# Memory.net
KiCad netlist of a schematic drawn in Altium Designer
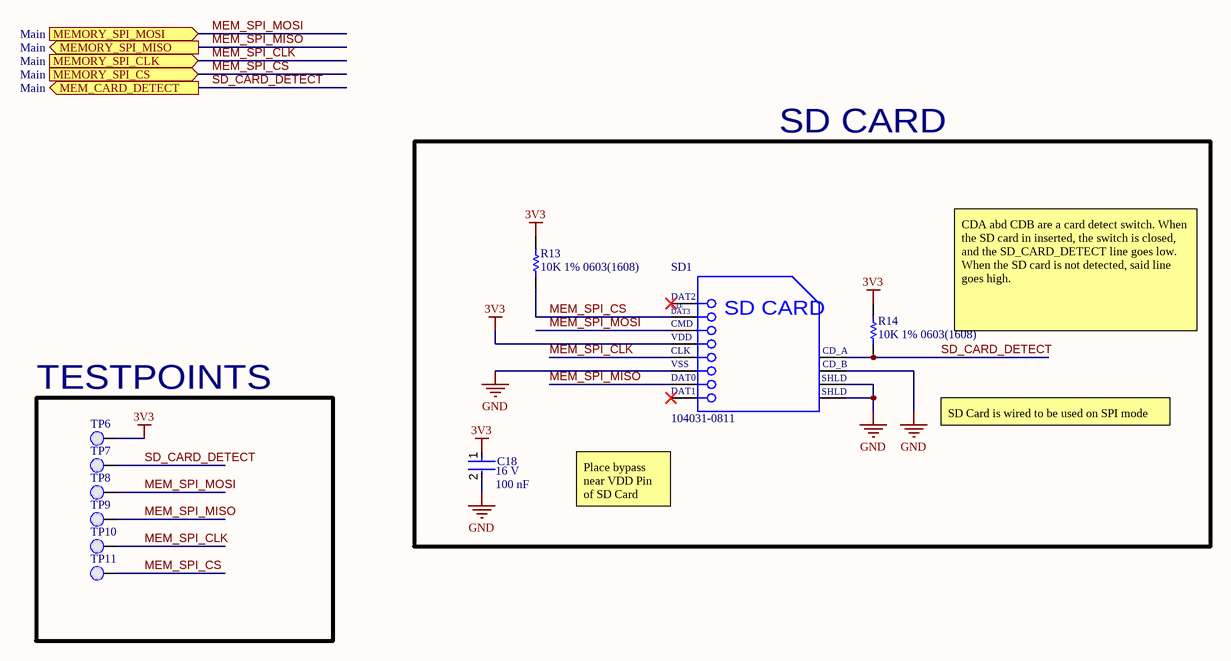
[diagram p0: Memory.SchDoc]

(export (version "E")
  (design (tool "Eeschema 10.0.6"))
  (components
    (comp (ref "C18")
      (value "100 nF")
      (footprint "FP-CC0603-DA-MFG")
      (description "CAP CER 0.1UF 16V X7R 0603")
      (fields
        (field (name "TOLERANCE") "0.1")
        (field (name "VOLTAGE") "16 V")
        (field (name "MANUFACTURER") "YAGEO")
      )
      (libsource (lib "Altium Content Vault") (part "11868f565c42a9108669ba33697ecf6"))
    )
    (comp (ref "R13")
      (value "10K 1% 0603(1608)")
      (footprint "RESC0603(1608)_N")
      (description "10K 0.1W 1% 0603 (1608 Metric)  SMD")
      (fields (field (name "POWER") "0.1 W") (field (name "TOLERANCE") "1 %"))
      (libsource (lib "Altium Content Vault") (part "RES"))
    )
    (comp (ref "R14")
      (value "10K 1% 0603(1608)")
      (footprint "RESC0603(1608)_N")
      (description "10K 0.1W 1% 0603 (1608 Metric)  SMD")
      (fields (field (name "POWER") "0.1 W") (field (name "TOLERANCE") "1 %"))
      (libsource (lib "Altium Content Vault") (part "RES"))
    )
    (comp (ref "SD1")
      (value "104031-0811")
      (footprint "MOLX-104031-0811_V")
      (description "Micro SD Card, RA, -25 to 85 degC, 8-Pin SMD, RoHS, Tape and Reel")
      (fields (field (name "MANUFACTURER") "Molex"))
      (libsource (lib "Altium Content Vault") (part "CN-SD-8-2SW-2S"))
    )
    (comp (ref "TP6")
      (value "0.1\" Pad")
      (footprint "PCBComponent")
      (libsource (lib "Components - 12.02.20 - 18.05") (part "0.1{dblquote} Pad-A.4"))
    )
    (comp (ref "TP7")
      (value "0.1\" Pad")
      (footprint "PCBComponent")
      (libsource (lib "Components - 12.02.20 - 18.05") (part "0.1{dblquote} Pad-A.4"))
    )
    (comp (ref "TP8")
      (value "0.1\" Pad")
      (footprint "PCBComponent")
      (libsource (lib "Components - 12.02.20 - 18.05") (part "0.1{dblquote} Pad-A.4"))
    )
    (comp (ref "TP9")
      (value "0.1\" Pad")
      (footprint "PCBComponent")
      (libsource (lib "Components - 12.02.20 - 18.05") (part "0.1{dblquote} Pad-A.4"))
    )
    (comp (ref "TP10")
      (value "0.1\" Pad")
      (footprint "PCBComponent")
      (libsource (lib "Components - 12.02.20 - 18.05") (part "0.1{dblquote} Pad-A.4"))
    )
    (comp (ref "TP11")
      (value "0.1\" Pad")
      (footprint "PCBComponent")
      (libsource (lib "Components - 12.02.20 - 18.05") (part "0.1{dblquote} Pad-A.4"))
    )
  )
  (nets
    (net (code "1") (name "/MEM_SPI_CLK") (class "Default")
      (node (ref "SD1") (pin "5") (pinfunction "CLK_5") (pintype "passive"))
      (node (ref "TP10") (pin "1") (pinfunction "PAD_1") (pintype "passive"))
    )
    (net (code "2") (name "/MEM_SPI_CS") (class "Default")
      (node (ref "R13") (pin "1") (pinfunction "1_1") (pintype "passive"))
      (node (ref "SD1") (pin "2") (pinfunction "CMD_2") (pintype "passive"))
      (node (ref "TP11") (pin "1") (pinfunction "PAD_1") (pintype "passive"))
    )
    (net (code "3") (name "/MEM_SPI_MISO") (class "Default")
      (node (ref "SD1") (pin "7") (pinfunction "DAT0_7") (pintype "passive"))
      (node (ref "TP9") (pin "1") (pinfunction "PAD_1") (pintype "passive"))
    )
    (net (code "4") (name "/MEM_SPI_MOSI") (class "Default")
      (node (ref "SD1") (pin "3") (pinfunction "VSS1_3") (pintype "passive"))
      (node (ref "TP8") (pin "1") (pinfunction "PAD_1") (pintype "passive"))
    )
    (net (code "5") (name "/SD_CARD_DETECT") (class "Default")
      (node (ref "R14") (pin "1") (pinfunction "1_1") (pintype "passive"))
      (node (ref "SD1") (pin "9") (pinfunction "CD_A_9") (pintype "passive"))
      (node (ref "TP7") (pin "1") (pinfunction "PAD_1") (pintype "passive"))
    )
    (net (code "6") (name "3V3") (class "Default")
      (node (ref "C18") (pin "1") (pinfunction "1_1") (pintype "passive"))
      (node (ref "R13") (pin "2") (pinfunction "2_2") (pintype "passive"))
      (node (ref "R14") (pin "2") (pinfunction "2_2") (pintype "passive"))
      (node (ref "SD1") (pin "4") (pinfunction "VDD_4") (pintype "passive"))
      (node (ref "TP6") (pin "1") (pinfunction "PAD_1") (pintype "passive"))
    )
    (net (code "7") (name "GND") (class "Default")
      (node (ref "C18") (pin "2") (pinfunction "2_2") (pintype "passive"))
      (node (ref "SD1") (pin "10") (pinfunction "CD_B_10") (pintype "passive"))
      (node (ref "SD1") (pin "11") (pinfunction "SHLD1_11") (pintype "passive"))
      (node (ref "SD1") (pin "12") (pinfunction "SHLD2_12") (pintype "passive"))
      (node (ref "SD1") (pin "6") (pinfunction "VSS2_6") (pintype "passive"))
    )
    (net (code "8") (name "unconnected-(SD1-CD{slash}DAT3-Pad1)") (class "Default")
      (node (ref "SD1") (pin "1") (pinfunction "CD/DAT3_1") (pintype "passive+no_connect"))
    )
    (net (code "9") (name "unconnected-(SD1-DAT1-Pad8)") (class "Default")
      (node (ref "SD1") (pin "8") (pinfunction "DAT1_8") (pintype "passive+no_connect"))
    )
  )
)
